# Multiplexage_Matrices.net
KiCad netlist of a schematic drawn in Altium Designer
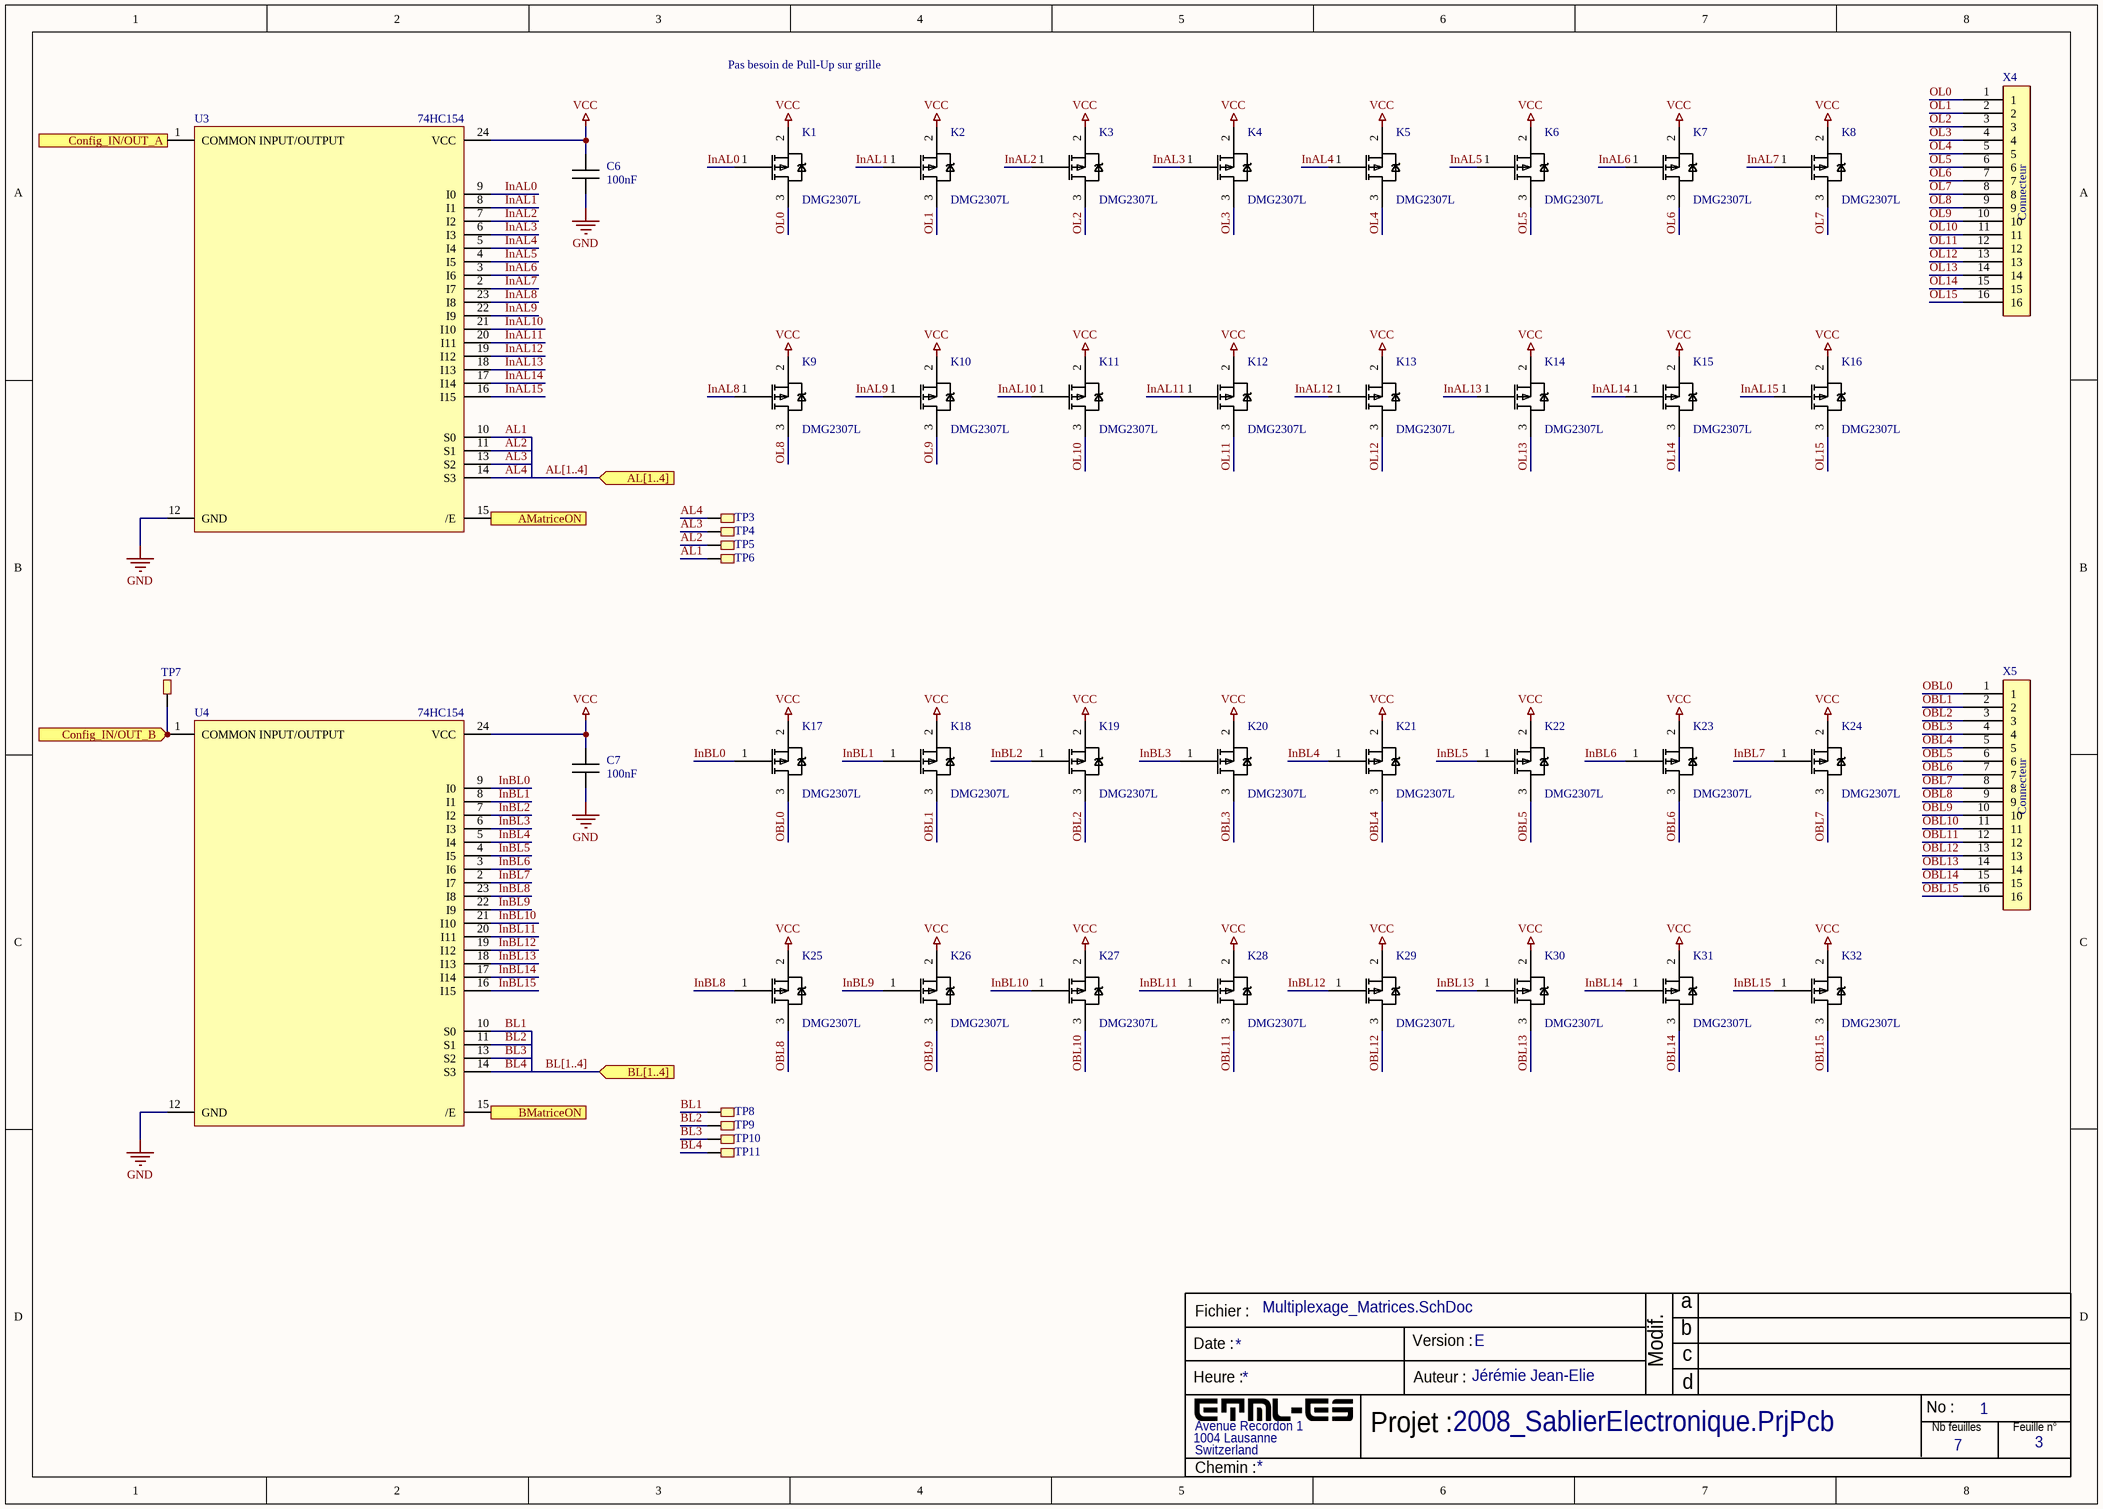
[diagram p0: Multiplexage_Matrices.SchDoc]

(export (version "E")
  (design (tool "Eeschema 10.0.6"))
  (components
    (comp (ref "C6")
      (value "100nF")
      (footprint "CAPC1608X08M")
      (description "CAPC 100nF X7R 50V 10% 1608 (0603 INCH)")
      (fields (field (name "VOLTAGE") "50V") (field (name "MANUFACTURER") "TDK"))
      (libsource (lib "ETML-ES") (part "CAP"))
    )
    (comp (ref "C7")
      (value "100nF")
      (footprint "CAPC1608X08M")
      (description "CAPC 100nF X7R 50V 10% 1608 (0603 INCH)")
      (fields (field (name "VOLTAGE") "50V") (field (name "MANUFACTURER") "TDK"))
      (libsource (lib "ETML-ES") (part "CAP"))
    )
    (comp (ref "K1")
      (value "DMG2307L")
      (footprint "SOT90P240X110-3M")
      (description "TRAN DMG2307L P-Channel Enhancement MOSFET 30V 2.5A")
      (fields (field (name "POWER") "760mW") (field (name "MANUFACTURER") "Diodes Incorporated"))
      (libsource (lib "ETML-ES") (part "TRAN-MOS-E-P-GSD"))
    )
    (comp (ref "K2")
      (value "DMG2307L")
      (footprint "SOT90P240X110-3M")
      (description "TRAN DMG2307L P-Channel Enhancement MOSFET 30V 2.5A")
      (fields (field (name "POWER") "760mW") (field (name "MANUFACTURER") "Diodes Incorporated"))
      (libsource (lib "ETML-ES") (part "TRAN-MOS-E-P-GSD"))
    )
    (comp (ref "K3")
      (value "DMG2307L")
      (footprint "SOT90P240X110-3M")
      (description "TRAN DMG2307L P-Channel Enhancement MOSFET 30V 2.5A")
      (fields (field (name "POWER") "760mW") (field (name "MANUFACTURER") "Diodes Incorporated"))
      (libsource (lib "ETML-ES") (part "TRAN-MOS-E-P-GSD"))
    )
    (comp (ref "K4")
      (value "DMG2307L")
      (footprint "SOT90P240X110-3M")
      (description "TRAN DMG2307L P-Channel Enhancement MOSFET 30V 2.5A")
      (fields (field (name "POWER") "760mW") (field (name "MANUFACTURER") "Diodes Incorporated"))
      (libsource (lib "ETML-ES") (part "TRAN-MOS-E-P-GSD"))
    )
    (comp (ref "K5")
      (value "DMG2307L")
      (footprint "SOT90P240X110-3M")
      (description "TRAN DMG2307L P-Channel Enhancement MOSFET 30V 2.5A")
      (fields (field (name "POWER") "760mW") (field (name "MANUFACTURER") "Diodes Incorporated"))
      (libsource (lib "ETML-ES") (part "TRAN-MOS-E-P-GSD"))
    )
    (comp (ref "K6")
      (value "DMG2307L")
      (footprint "SOT90P240X110-3M")
      (description "TRAN DMG2307L P-Channel Enhancement MOSFET 30V 2.5A")
      (fields (field (name "POWER") "760mW") (field (name "MANUFACTURER") "Diodes Incorporated"))
      (libsource (lib "ETML-ES") (part "TRAN-MOS-E-P-GSD"))
    )
    (comp (ref "K7")
      (value "DMG2307L")
      (footprint "SOT90P240X110-3M")
      (description "TRAN DMG2307L P-Channel Enhancement MOSFET 30V 2.5A")
      (fields (field (name "POWER") "760mW") (field (name "MANUFACTURER") "Diodes Incorporated"))
      (libsource (lib "ETML-ES") (part "TRAN-MOS-E-P-GSD"))
    )
    (comp (ref "K8")
      (value "DMG2307L")
      (footprint "SOT90P240X110-3M")
      (description "TRAN DMG2307L P-Channel Enhancement MOSFET 30V 2.5A")
      (fields (field (name "POWER") "760mW") (field (name "MANUFACTURER") "Diodes Incorporated"))
      (libsource (lib "ETML-ES") (part "TRAN-MOS-E-P-GSD"))
    )
    (comp (ref "K9")
      (value "DMG2307L")
      (footprint "SOT90P240X110-3M")
      (description "TRAN DMG2307L P-Channel Enhancement MOSFET 30V 2.5A")
      (fields (field (name "POWER") "760mW") (field (name "MANUFACTURER") "Diodes Incorporated"))
      (libsource (lib "ETML-ES") (part "TRAN-MOS-E-P-GSD"))
    )
    (comp (ref "K10")
      (value "DMG2307L")
      (footprint "SOT90P240X110-3M")
      (description "TRAN DMG2307L P-Channel Enhancement MOSFET 30V 2.5A")
      (fields (field (name "POWER") "760mW") (field (name "MANUFACTURER") "Diodes Incorporated"))
      (libsource (lib "ETML-ES") (part "TRAN-MOS-E-P-GSD"))
    )
    (comp (ref "K11")
      (value "DMG2307L")
      (footprint "SOT90P240X110-3M")
      (description "TRAN DMG2307L P-Channel Enhancement MOSFET 30V 2.5A")
      (fields (field (name "POWER") "760mW") (field (name "MANUFACTURER") "Diodes Incorporated"))
      (libsource (lib "ETML-ES") (part "TRAN-MOS-E-P-GSD"))
    )
    (comp (ref "K12")
      (value "DMG2307L")
      (footprint "SOT90P240X110-3M")
      (description "TRAN DMG2307L P-Channel Enhancement MOSFET 30V 2.5A")
      (fields (field (name "POWER") "760mW") (field (name "MANUFACTURER") "Diodes Incorporated"))
      (libsource (lib "ETML-ES") (part "TRAN-MOS-E-P-GSD"))
    )
    (comp (ref "K13")
      (value "DMG2307L")
      (footprint "SOT90P240X110-3M")
      (description "TRAN DMG2307L P-Channel Enhancement MOSFET 30V 2.5A")
      (fields (field (name "POWER") "760mW") (field (name "MANUFACTURER") "Diodes Incorporated"))
      (libsource (lib "ETML-ES") (part "TRAN-MOS-E-P-GSD"))
    )
    (comp (ref "K14")
      (value "DMG2307L")
      (footprint "SOT90P240X110-3M")
      (description "TRAN DMG2307L P-Channel Enhancement MOSFET 30V 2.5A")
      (fields (field (name "POWER") "760mW") (field (name "MANUFACTURER") "Diodes Incorporated"))
      (libsource (lib "ETML-ES") (part "TRAN-MOS-E-P-GSD"))
    )
    (comp (ref "K15")
      (value "DMG2307L")
      (footprint "SOT90P240X110-3M")
      (description "TRAN DMG2307L P-Channel Enhancement MOSFET 30V 2.5A")
      (fields (field (name "POWER") "760mW") (field (name "MANUFACTURER") "Diodes Incorporated"))
      (libsource (lib "ETML-ES") (part "TRAN-MOS-E-P-GSD"))
    )
    (comp (ref "K16")
      (value "DMG2307L")
      (footprint "SOT90P240X110-3M")
      (description "TRAN DMG2307L P-Channel Enhancement MOSFET 30V 2.5A")
      (fields (field (name "POWER") "760mW") (field (name "MANUFACTURER") "Diodes Incorporated"))
      (libsource (lib "ETML-ES") (part "TRAN-MOS-E-P-GSD"))
    )
    (comp (ref "K17")
      (value "DMG2307L")
      (footprint "SOT90P240X110-3M")
      (description "TRAN DMG2307L P-Channel Enhancement MOSFET 30V 2.5A")
      (fields (field (name "POWER") "760mW") (field (name "MANUFACTURER") "Diodes Incorporated"))
      (libsource (lib "ETML-ES") (part "TRAN-MOS-E-P-GSD"))
    )
    (comp (ref "K18")
      (value "DMG2307L")
      (footprint "SOT90P240X110-3M")
      (description "TRAN DMG2307L P-Channel Enhancement MOSFET 30V 2.5A")
      (fields (field (name "POWER") "760mW") (field (name "MANUFACTURER") "Diodes Incorporated"))
      (libsource (lib "ETML-ES") (part "TRAN-MOS-E-P-GSD"))
    )
    (comp (ref "K19")
      (value "DMG2307L")
      (footprint "SOT90P240X110-3M")
      (description "TRAN DMG2307L P-Channel Enhancement MOSFET 30V 2.5A")
      (fields (field (name "POWER") "760mW") (field (name "MANUFACTURER") "Diodes Incorporated"))
      (libsource (lib "ETML-ES") (part "TRAN-MOS-E-P-GSD"))
    )
    (comp (ref "K20")
      (value "DMG2307L")
      (footprint "SOT90P240X110-3M")
      (description "TRAN DMG2307L P-Channel Enhancement MOSFET 30V 2.5A")
      (fields (field (name "POWER") "760mW") (field (name "MANUFACTURER") "Diodes Incorporated"))
      (libsource (lib "ETML-ES") (part "TRAN-MOS-E-P-GSD"))
    )
    (comp (ref "K21")
      (value "DMG2307L")
      (footprint "SOT90P240X110-3M")
      (description "TRAN DMG2307L P-Channel Enhancement MOSFET 30V 2.5A")
      (fields (field (name "POWER") "760mW") (field (name "MANUFACTURER") "Diodes Incorporated"))
      (libsource (lib "ETML-ES") (part "TRAN-MOS-E-P-GSD"))
    )
    (comp (ref "K22")
      (value "DMG2307L")
      (footprint "SOT90P240X110-3M")
      (description "TRAN DMG2307L P-Channel Enhancement MOSFET 30V 2.5A")
      (fields (field (name "POWER") "760mW") (field (name "MANUFACTURER") "Diodes Incorporated"))
      (libsource (lib "ETML-ES") (part "TRAN-MOS-E-P-GSD"))
    )
    (comp (ref "K23")
      (value "DMG2307L")
      (footprint "SOT90P240X110-3M")
      (description "TRAN DMG2307L P-Channel Enhancement MOSFET 30V 2.5A")
      (fields (field (name "POWER") "760mW") (field (name "MANUFACTURER") "Diodes Incorporated"))
      (libsource (lib "ETML-ES") (part "TRAN-MOS-E-P-GSD"))
    )
    (comp (ref "K24")
      (value "DMG2307L")
      (footprint "SOT90P240X110-3M")
      (description "TRAN DMG2307L P-Channel Enhancement MOSFET 30V 2.5A")
      (fields (field (name "POWER") "760mW") (field (name "MANUFACTURER") "Diodes Incorporated"))
      (libsource (lib "ETML-ES") (part "TRAN-MOS-E-P-GSD"))
    )
    (comp (ref "K25")
      (value "DMG2307L")
      (footprint "SOT90P240X110-3M")
      (description "TRAN DMG2307L P-Channel Enhancement MOSFET 30V 2.5A")
      (fields (field (name "POWER") "760mW") (field (name "MANUFACTURER") "Diodes Incorporated"))
      (libsource (lib "ETML-ES") (part "TRAN-MOS-E-P-GSD"))
    )
    (comp (ref "K26")
      (value "DMG2307L")
      (footprint "SOT90P240X110-3M")
      (description "TRAN DMG2307L P-Channel Enhancement MOSFET 30V 2.5A")
      (fields (field (name "POWER") "760mW") (field (name "MANUFACTURER") "Diodes Incorporated"))
      (libsource (lib "ETML-ES") (part "TRAN-MOS-E-P-GSD"))
    )
    (comp (ref "K27")
      (value "DMG2307L")
      (footprint "SOT90P240X110-3M")
      (description "TRAN DMG2307L P-Channel Enhancement MOSFET 30V 2.5A")
      (fields (field (name "POWER") "760mW") (field (name "MANUFACTURER") "Diodes Incorporated"))
      (libsource (lib "ETML-ES") (part "TRAN-MOS-E-P-GSD"))
    )
    (comp (ref "K28")
      (value "DMG2307L")
      (footprint "SOT90P240X110-3M")
      (description "TRAN DMG2307L P-Channel Enhancement MOSFET 30V 2.5A")
      (fields (field (name "POWER") "760mW") (field (name "MANUFACTURER") "Diodes Incorporated"))
      (libsource (lib "ETML-ES") (part "TRAN-MOS-E-P-GSD"))
    )
    (comp (ref "K29")
      (value "DMG2307L")
      (footprint "SOT90P240X110-3M")
      (description "TRAN DMG2307L P-Channel Enhancement MOSFET 30V 2.5A")
      (fields (field (name "POWER") "760mW") (field (name "MANUFACTURER") "Diodes Incorporated"))
      (libsource (lib "ETML-ES") (part "TRAN-MOS-E-P-GSD"))
    )
    (comp (ref "K30")
      (value "DMG2307L")
      (footprint "SOT90P240X110-3M")
      (description "TRAN DMG2307L P-Channel Enhancement MOSFET 30V 2.5A")
      (fields (field (name "POWER") "760mW") (field (name "MANUFACTURER") "Diodes Incorporated"))
      (libsource (lib "ETML-ES") (part "TRAN-MOS-E-P-GSD"))
    )
    (comp (ref "K31")
      (value "DMG2307L")
      (footprint "SOT90P240X110-3M")
      (description "TRAN DMG2307L P-Channel Enhancement MOSFET 30V 2.5A")
      (fields (field (name "POWER") "760mW") (field (name "MANUFACTURER") "Diodes Incorporated"))
      (libsource (lib "ETML-ES") (part "TRAN-MOS-E-P-GSD"))
    )
    (comp (ref "K32")
      (value "DMG2307L")
      (footprint "SOT90P240X110-3M")
      (description "TRAN DMG2307L P-Channel Enhancement MOSFET 30V 2.5A")
      (fields (field (name "POWER") "760mW") (field (name "MANUFACTURER") "Diodes Incorporated"))
      (libsource (lib "ETML-ES") (part "TRAN-MOS-E-P-GSD"))
    )
    (comp (ref "TP3")
      (value "TestPoint")
      (footprint "KEYSTONE_5019")
      (libsource (lib "Schlib1") (part "TestPoint"))
    )
    (comp (ref "TP4")
      (value "TestPoint")
      (footprint "KEYSTONE_5019")
      (libsource (lib "Schlib1") (part "TestPoint"))
    )
    (comp (ref "TP5")
      (value "TestPoint")
      (footprint "KEYSTONE_5019")
      (libsource (lib "Schlib1") (part "TestPoint"))
    )
    (comp (ref "TP6")
      (value "TestPoint")
      (footprint "KEYSTONE_5019")
      (libsource (lib "Schlib1") (part "TestPoint"))
    )
    (comp (ref "TP7") (value "5019") (footprint "KEYSTONE_5019") (libsource (lib "") (part "TestPoint_1")))
    (comp (ref "TP8")
      (value "TestPoint")
      (footprint "KEYSTONE_5019")
      (libsource (lib "Schlib1") (part "TestPoint"))
    )
    (comp (ref "TP9")
      (value "TestPoint")
      (footprint "KEYSTONE_5019")
      (libsource (lib "Schlib1") (part "TestPoint"))
    )
    (comp (ref "TP10")
      (value "TestPoint")
      (footprint "KEYSTONE_5019")
      (libsource (lib "Schlib1") (part "TestPoint"))
    )
    (comp (ref "TP11")
      (value "TestPoint")
      (footprint "KEYSTONE_5019")
      (libsource (lib "Schlib1") (part "TestPoint"))
    )
    (comp (ref "U3")
      (value "74HC154")
      (footprint "SOP127P1030X265-24N")
      (libsource (lib "Schlib1") (part "74HC154"))
    )
    (comp (ref "U4")
      (value "74HC154")
      (footprint "SOP127P1030X265-24N")
      (libsource (lib "Schlib1") (part "74HC154"))
    )
    (comp (ref "X4")
      (value "~")
      (footprint "MOLEX_2x8")
      (libsource (lib "2008_SablierElectronique_SCHLIB") (part "Mâle DIN 8 x 8"))
    )
    (comp (ref "X5")
      (value "~")
      (footprint "MOLEX_2x8")
      (libsource (lib "2008_SablierElectronique_SCHLIB") (part "Mâle DIN 8 x 8"))
    )
  )
  (nets
    (net (code "1") (name "/AL1") (class "Default")
      (node (ref "TP6") (pin "1") (pinfunction "1_1") (pintype "passive"))
      (node (ref "U3") (pin "10") (pinfunction "S0_10") (pintype "passive"))
    )
    (net (code "2") (name "/AL2") (class "Default")
      (node (ref "TP5") (pin "1") (pinfunction "1_1") (pintype "passive"))
      (node (ref "U3") (pin "11") (pinfunction "S1_11") (pintype "passive"))
    )
    (net (code "3") (name "/AL3") (class "Default")
      (node (ref "TP4") (pin "1") (pinfunction "1_1") (pintype "passive"))
      (node (ref "U3") (pin "13") (pinfunction "S2_13") (pintype "passive"))
    )
    (net (code "4") (name "/AL4") (class "Default")
      (node (ref "TP3") (pin "1") (pinfunction "1_1") (pintype "passive"))
      (node (ref "U3") (pin "14") (pinfunction "S3_14") (pintype "passive"))
    )
    (net (code "6") (name "/AMatriceON") (class "Default")
      (node (ref "U3") (pin "15") (pinfunction "/E_15") (pintype "passive"))
    )
    (net (code "7") (name "/BL1") (class "Default")
      (node (ref "TP8") (pin "1") (pinfunction "1_1") (pintype "passive"))
      (node (ref "U4") (pin "10") (pinfunction "S0_10") (pintype "passive"))
    )
    (net (code "8") (name "/BL2") (class "Default")
      (node (ref "TP9") (pin "1") (pinfunction "1_1") (pintype "passive"))
      (node (ref "U4") (pin "11") (pinfunction "S1_11") (pintype "passive"))
    )
    (net (code "9") (name "/BL3") (class "Default")
      (node (ref "TP10") (pin "1") (pinfunction "1_1") (pintype "passive"))
      (node (ref "U4") (pin "13") (pinfunction "S2_13") (pintype "passive"))
    )
    (net (code "10") (name "/BL4") (class "Default")
      (node (ref "TP11") (pin "1") (pinfunction "1_1") (pintype "passive"))
      (node (ref "U4") (pin "14") (pinfunction "S3_14") (pintype "passive"))
    )
    (net (code "12") (name "/BMatriceON") (class "Default")
      (node (ref "U4") (pin "15") (pinfunction "/E_15") (pintype "passive"))
    )
    (net (code "13") (name "/Config_IN{slash}OUT_A") (class "Default")
      (node (ref "U3") (pin "1") (pinfunction "COMMON_INPUT/OUTPUT_1") (pintype "passive"))
    )
    (net (code "14") (name "/Config_IN{slash}OUT_B") (class "Default")
      (node (ref "TP7") (pin "1") (pinfunction "1_1") (pintype "passive"))
      (node (ref "U4") (pin "1") (pinfunction "COMMON_INPUT/OUTPUT_1") (pintype "passive"))
    )
    (net (code "15") (name "/InAL0") (class "Default")
      (node (ref "K1") (pin "1") (pinfunction "G_1") (pintype "passive"))
      (node (ref "U3") (pin "9") (pinfunction "I0_9") (pintype "passive"))
    )
    (net (code "16") (name "/InAL1") (class "Default")
      (node (ref "K2") (pin "1") (pinfunction "G_1") (pintype "passive"))
      (node (ref "U3") (pin "8") (pinfunction "I1_8") (pintype "passive"))
    )
    (net (code "17") (name "/InAL2") (class "Default")
      (node (ref "K3") (pin "1") (pinfunction "G_1") (pintype "passive"))
      (node (ref "U3") (pin "7") (pinfunction "I2_7") (pintype "passive"))
    )
    (net (code "18") (name "/InAL3") (class "Default")
      (node (ref "K4") (pin "1") (pinfunction "G_1") (pintype "passive"))
      (node (ref "U3") (pin "6") (pinfunction "I3_6") (pintype "passive"))
    )
    (net (code "19") (name "/InAL4") (class "Default")
      (node (ref "K5") (pin "1") (pinfunction "G_1") (pintype "passive"))
      (node (ref "U3") (pin "5") (pinfunction "I4_5") (pintype "passive"))
    )
    (net (code "20") (name "/InAL5") (class "Default")
      (node (ref "K6") (pin "1") (pinfunction "G_1") (pintype "passive"))
      (node (ref "U3") (pin "4") (pinfunction "I5_4") (pintype "passive"))
    )
    (net (code "21") (name "/InAL6") (class "Default")
      (node (ref "K7") (pin "1") (pinfunction "G_1") (pintype "passive"))
      (node (ref "U3") (pin "3") (pinfunction "I6_3") (pintype "passive"))
    )
    (net (code "22") (name "/InAL7") (class "Default")
      (node (ref "K8") (pin "1") (pinfunction "G_1") (pintype "passive"))
      (node (ref "U3") (pin "2") (pinfunction "I7_2") (pintype "passive"))
    )
    (net (code "23") (name "/InAL8") (class "Default")
      (node (ref "K9") (pin "1") (pinfunction "G_1") (pintype "passive"))
      (node (ref "U3") (pin "23") (pinfunction "I8_23") (pintype "passive"))
    )
    (net (code "24") (name "/InAL9") (class "Default")
      (node (ref "K10") (pin "1") (pinfunction "G_1") (pintype "passive"))
      (node (ref "U3") (pin "22") (pinfunction "I9_22") (pintype "passive"))
    )
    (net (code "25") (name "/InAL10") (class "Default")
      (node (ref "K11") (pin "1") (pinfunction "G_1") (pintype "passive"))
      (node (ref "U3") (pin "21") (pinfunction "I10_21") (pintype "passive"))
    )
    (net (code "26") (name "/InAL11") (class "Default")
      (node (ref "K12") (pin "1") (pinfunction "G_1") (pintype "passive"))
      (node (ref "U3") (pin "20") (pinfunction "I11_20") (pintype "passive"))
    )
    (net (code "27") (name "/InAL12") (class "Default")
      (node (ref "K13") (pin "1") (pinfunction "G_1") (pintype "passive"))
      (node (ref "U3") (pin "19") (pinfunction "I12_19") (pintype "passive"))
    )
    (net (code "28") (name "/InAL13") (class "Default")
      (node (ref "K14") (pin "1") (pinfunction "G_1") (pintype "passive"))
      (node (ref "U3") (pin "18") (pinfunction "I13_18") (pintype "passive"))
    )
    (net (code "29") (name "/InAL14") (class "Default")
      (node (ref "K15") (pin "1") (pinfunction "G_1") (pintype "passive"))
      (node (ref "U3") (pin "17") (pinfunction "I14_17") (pintype "passive"))
    )
    (net (code "30") (name "/InAL15") (class "Default")
      (node (ref "K16") (pin "1") (pinfunction "G_1") (pintype "passive"))
      (node (ref "U3") (pin "16") (pinfunction "I15_16") (pintype "passive"))
    )
    (net (code "31") (name "/InBL0") (class "Default")
      (node (ref "K17") (pin "1") (pinfunction "G_1") (pintype "passive"))
      (node (ref "U4") (pin "9") (pinfunction "I0_9") (pintype "passive"))
    )
    (net (code "32") (name "/InBL1") (class "Default")
      (node (ref "K18") (pin "1") (pinfunction "G_1") (pintype "passive"))
      (node (ref "U4") (pin "8") (pinfunction "I1_8") (pintype "passive"))
    )
    (net (code "33") (name "/InBL2") (class "Default")
      (node (ref "K19") (pin "1") (pinfunction "G_1") (pintype "passive"))
      (node (ref "U4") (pin "7") (pinfunction "I2_7") (pintype "passive"))
    )
    (net (code "34") (name "/InBL3") (class "Default")
      (node (ref "K20") (pin "1") (pinfunction "G_1") (pintype "passive"))
      (node (ref "U4") (pin "6") (pinfunction "I3_6") (pintype "passive"))
    )
    (net (code "35") (name "/InBL4") (class "Default")
      (node (ref "K21") (pin "1") (pinfunction "G_1") (pintype "passive"))
      (node (ref "U4") (pin "5") (pinfunction "I4_5") (pintype "passive"))
    )
    (net (code "36") (name "/InBL5") (class "Default")
      (node (ref "K22") (pin "1") (pinfunction "G_1") (pintype "passive"))
      (node (ref "U4") (pin "4") (pinfunction "I5_4") (pintype "passive"))
    )
    (net (code "37") (name "/InBL6") (class "Default")
      (node (ref "K23") (pin "1") (pinfunction "G_1") (pintype "passive"))
      (node (ref "U4") (pin "3") (pinfunction "I6_3") (pintype "passive"))
    )
    (net (code "38") (name "/InBL7") (class "Default")
      (node (ref "K24") (pin "1") (pinfunction "G_1") (pintype "passive"))
      (node (ref "U4") (pin "2") (pinfunction "I7_2") (pintype "passive"))
    )
    (net (code "39") (name "/InBL8") (class "Default")
      (node (ref "K25") (pin "1") (pinfunction "G_1") (pintype "passive"))
      (node (ref "U4") (pin "23") (pinfunction "I8_23") (pintype "passive"))
    )
    (net (code "40") (name "/InBL9") (class "Default")
      (node (ref "K26") (pin "1") (pinfunction "G_1") (pintype "passive"))
      (node (ref "U4") (pin "22") (pinfunction "I9_22") (pintype "passive"))
    )
    (net (code "41") (name "/InBL10") (class "Default")
      (node (ref "K27") (pin "1") (pinfunction "G_1") (pintype "passive"))
      (node (ref "U4") (pin "21") (pinfunction "I10_21") (pintype "passive"))
    )
    (net (code "42") (name "/InBL11") (class "Default")
      (node (ref "K28") (pin "1") (pinfunction "G_1") (pintype "passive"))
      (node (ref "U4") (pin "20") (pinfunction "I11_20") (pintype "passive"))
    )
    (net (code "43") (name "/InBL12") (class "Default")
      (node (ref "K29") (pin "1") (pinfunction "G_1") (pintype "passive"))
      (node (ref "U4") (pin "19") (pinfunction "I12_19") (pintype "passive"))
    )
    (net (code "44") (name "/InBL13") (class "Default")
      (node (ref "K30") (pin "1") (pinfunction "G_1") (pintype "passive"))
      (node (ref "U4") (pin "18") (pinfunction "I13_18") (pintype "passive"))
    )
    (net (code "45") (name "/InBL14") (class "Default")
      (node (ref "K31") (pin "1") (pinfunction "G_1") (pintype "passive"))
      (node (ref "U4") (pin "17") (pinfunction "I14_17") (pintype "passive"))
    )
    (net (code "46") (name "/InBL15") (class "Default")
      (node (ref "K32") (pin "1") (pinfunction "G_1") (pintype "passive"))
      (node (ref "U4") (pin "16") (pinfunction "I15_16") (pintype "passive"))
    )
    (net (code "47") (name "/OBL0") (class "Default")
      (node (ref "K17") (pin "3") (pinfunction "D_3") (pintype "passive"))
      (node (ref "X5") (pin "1") (pinfunction "1_1") (pintype "passive"))
    )
    (net (code "48") (name "/OBL1") (class "Default")
      (node (ref "K18") (pin "3") (pinfunction "D_3") (pintype "passive"))
      (node (ref "X5") (pin "2") (pinfunction "2_2") (pintype "passive"))
    )
    (net (code "49") (name "/OBL2") (class "Default")
      (node (ref "K19") (pin "3") (pinfunction "D_3") (pintype "passive"))
      (node (ref "X5") (pin "3") (pinfunction "3_3") (pintype "passive"))
    )
    (net (code "50") (name "/OBL3") (class "Default")
      (node (ref "K20") (pin "3") (pinfunction "D_3") (pintype "passive"))
      (node (ref "X5") (pin "4") (pinfunction "4_4") (pintype "passive"))
    )
    (net (code "51") (name "/OBL4") (class "Default")
      (node (ref "K21") (pin "3") (pinfunction "D_3") (pintype "passive"))
      (node (ref "X5") (pin "5") (pinfunction "5_5") (pintype "passive"))
    )
    (net (code "52") (name "/OBL5") (class "Default")
      (node (ref "K22") (pin "3") (pinfunction "D_3") (pintype "passive"))
      (node (ref "X5") (pin "6") (pinfunction "6_6") (pintype "passive"))
    )
    (net (code "53") (name "/OBL6") (class "Default")
      (node (ref "K23") (pin "3") (pinfunction "D_3") (pintype "passive"))
      (node (ref "X5") (pin "7") (pinfunction "7_7") (pintype "passive"))
    )
    (net (code "54") (name "/OBL7") (class "Default")
      (node (ref "K24") (pin "3") (pinfunction "D_3") (pintype "passive"))
      (node (ref "X5") (pin "8") (pinfunction "8_8") (pintype "passive"))
    )
    (net (code "55") (name "/OBL8") (class "Default")
      (node (ref "K25") (pin "3") (pinfunction "D_3") (pintype "passive"))
      (node (ref "X5") (pin "9") (pinfunction "9_9") (pintype "passive"))
    )
    (net (code "56") (name "/OBL9") (class "Default")
      (node (ref "K26") (pin "3") (pinfunction "D_3") (pintype "passive"))
      (node (ref "X5") (pin "10") (pinfunction "10_10") (pintype "passive"))
    )
    (net (code "57") (name "/OBL10") (class "Default")
      (node (ref "K27") (pin "3") (pinfunction "D_3") (pintype "passive"))
      (node (ref "X5") (pin "11") (pinfunction "11_11") (pintype "passive"))
    )
    (net (code "58") (name "/OBL11") (class "Default")
      (node (ref "K28") (pin "3") (pinfunction "D_3") (pintype "passive"))
      (node (ref "X5") (pin "12") (pinfunction "12_12") (pintype "passive"))
    )
    (net (code "59") (name "/OBL12") (class "Default")
      (node (ref "K29") (pin "3") (pinfunction "D_3") (pintype "passive"))
      (node (ref "X5") (pin "13") (pinfunction "13_13") (pintype "passive"))
    )
    (net (code "60") (name "/OBL13") (class "Default")
      (node (ref "K30") (pin "3") (pinfunction "D_3") (pintype "passive"))
      (node (ref "X5") (pin "14") (pinfunction "14_14") (pintype "passive"))
    )
    (net (code "61") (name "/OBL14") (class "Default")
      (node (ref "K31") (pin "3") (pinfunction "D_3") (pintype "passive"))
      (node (ref "X5") (pin "15") (pinfunction "15_15") (pintype "passive"))
    )
    (net (code "62") (name "/OBL15") (class "Default")
      (node (ref "K32") (pin "3") (pinfunction "D_3") (pintype "passive"))
      (node (ref "X5") (pin "16") (pinfunction "16_16") (pintype "passive"))
    )
    (net (code "63") (name "/OL0") (class "Default")
      (node (ref "K1") (pin "3") (pinfunction "D_3") (pintype "passive"))
      (node (ref "X4") (pin "1") (pinfunction "1_1") (pintype "passive"))
    )
    (net (code "64") (name "/OL1") (class "Default")
      (node (ref "K2") (pin "3") (pinfunction "D_3") (pintype "passive"))
      (node (ref "X4") (pin "2") (pinfunction "2_2") (pintype "passive"))
    )
    (net (code "65") (name "/OL2") (class "Default")
      (node (ref "K3") (pin "3") (pinfunction "D_3") (pintype "passive"))
      (node (ref "X4") (pin "3") (pinfunction "3_3") (pintype "passive"))
    )
    (net (code "66") (name "/OL3") (class "Default")
      (node (ref "K4") (pin "3") (pinfunction "D_3") (pintype "passive"))
      (node (ref "X4") (pin "4") (pinfunction "4_4") (pintype "passive"))
    )
    (net (code "67") (name "/OL4") (class "Default")
      (node (ref "K5") (pin "3") (pinfunction "D_3") (pintype "passive"))
      (node (ref "X4") (pin "5") (pinfunction "5_5") (pintype "passive"))
    )
    (net (code "68") (name "/OL5") (class "Default")
      (node (ref "K6") (pin "3") (pinfunction "D_3") (pintype "passive"))
      (node (ref "X4") (pin "6") (pinfunction "6_6") (pintype "passive"))
    )
    (net (code "69") (name "/OL6") (class "Default")
      (node (ref "K7") (pin "3") (pinfunction "D_3") (pintype "passive"))
      (node (ref "X4") (pin "7") (pinfunction "7_7") (pintype "passive"))
    )
    (net (code "70") (name "/OL7") (class "Default")
      (node (ref "K8") (pin "3") (pinfunction "D_3") (pintype "passive"))
      (node (ref "X4") (pin "8") (pinfunction "8_8") (pintype "passive"))
    )
    (net (code "71") (name "/OL8") (class "Default")
      (node (ref "K9") (pin "3") (pinfunction "D_3") (pintype "passive"))
      (node (ref "X4") (pin "9") (pinfunction "9_9") (pintype "passive"))
    )
    (net (code "72") (name "/OL9") (class "Default")
      (node (ref "K10") (pin "3") (pinfunction "D_3") (pintype "passive"))
      (node (ref "X4") (pin "10") (pinfunction "10_10") (pintype "passive"))
    )
    (net (code "73") (name "/OL10") (class "Default")
      (node (ref "K11") (pin "3") (pinfunction "D_3") (pintype "passive"))
      (node (ref "X4") (pin "11") (pinfunction "11_11") (pintype "passive"))
    )
    (net (code "74") (name "/OL11") (class "Default")
      (node (ref "K12") (pin "3") (pinfunction "D_3") (pintype "passive"))
      (node (ref "X4") (pin "12") (pinfunction "12_12") (pintype "passive"))
    )
    (net (code "75") (name "/OL12") (class "Default")
      (node (ref "K13") (pin "3") (pinfunction "D_3") (pintype "passive"))
      (node (ref "X4") (pin "13") (pinfunction "13_13") (pintype "passive"))
    )
    (net (code "76") (name "/OL13") (class "Default")
      (node (ref "K14") (pin "3") (pinfunction "D_3") (pintype "passive"))
      (node (ref "X4") (pin "14") (pinfunction "14_14") (pintype "passive"))
    )
    (net (code "77") (name "/OL14") (class "Default")
      (node (ref "K15") (pin "3") (pinfunction "D_3") (pintype "passive"))
      (node (ref "X4") (pin "15") (pinfunction "15_15") (pintype "passive"))
    )
    (net (code "78") (name "/OL15") (class "Default")
      (node (ref "K16") (pin "3") (pinfunction "D_3") (pintype "passive"))
      (node (ref "X4") (pin "16") (pinfunction "16_16") (pintype "passive"))
    )
    (net (code "79") (name "GND") (class "Default")
      (node (ref "C6") (pin "1") (pinfunction "1_1") (pintype "passive"))
      (node (ref "C7") (pin "1") (pinfunction "1_1") (pintype "passive"))
      (node (ref "U3") (pin "12") (pinfunction "GND_12") (pintype "passive"))
      (node (ref "U4") (pin "12") (pinfunction "GND_12") (pintype "passive"))
    )
    (net (code "80") (name "VCC") (class "Default")
      (node (ref "C6") (pin "2") (pinfunction "2_2") (pintype "passive"))
      (node (ref "C7") (pin "2") (pinfunction "2_2") (pintype "passive"))
      (node (ref "K1") (pin "2") (pinfunction "S_2") (pintype "passive"))
      (node (ref "K10") (pin "2") (pinfunction "S_2") (pintype "passive"))
      (node (ref "K11") (pin "2") (pinfunction "S_2") (pintype "passive"))
      (node (ref "K12") (pin "2") (pinfunction "S_2") (pintype "passive"))
      (node (ref "K13") (pin "2") (pinfunction "S_2") (pintype "passive"))
      (node (ref "K14") (pin "2") (pinfunction "S_2") (pintype "passive"))
      (node (ref "K15") (pin "2") (pinfunction "S_2") (pintype "passive"))
      (node (ref "K16") (pin "2") (pinfunction "S_2") (pintype "passive"))
      (node (ref "K17") (pin "2") (pinfunction "S_2") (pintype "passive"))
      (node (ref "K18") (pin "2") (pinfunction "S_2") (pintype "passive"))
      (node (ref "K19") (pin "2") (pinfunction "S_2") (pintype "passive"))
      (node (ref "K2") (pin "2") (pinfunction "S_2") (pintype "passive"))
      (node (ref "K20") (pin "2") (pinfunction "S_2") (pintype "passive"))
      (node (ref "K21") (pin "2") (pinfunction "S_2") (pintype "passive"))
      (node (ref "K22") (pin "2") (pinfunction "S_2") (pintype "passive"))
      (node (ref "K23") (pin "2") (pinfunction "S_2") (pintype "passive"))
      (node (ref "K24") (pin "2") (pinfunction "S_2") (pintype "passive"))
      (node (ref "K25") (pin "2") (pinfunction "S_2") (pintype "passive"))
      (node (ref "K26") (pin "2") (pinfunction "S_2") (pintype "passive"))
      (node (ref "K27") (pin "2") (pinfunction "S_2") (pintype "passive"))
      (node (ref "K28") (pin "2") (pinfunction "S_2") (pintype "passive"))
      (node (ref "K29") (pin "2") (pinfunction "S_2") (pintype "passive"))
      (node (ref "K3") (pin "2") (pinfunction "S_2") (pintype "passive"))
      (node (ref "K30") (pin "2") (pinfunction "S_2") (pintype "passive"))
      (node (ref "K31") (pin "2") (pinfunction "S_2") (pintype "passive"))
      (node (ref "K32") (pin "2") (pinfunction "S_2") (pintype "passive"))
      (node (ref "K4") (pin "2") (pinfunction "S_2") (pintype "passive"))
      (node (ref "K5") (pin "2") (pinfunction "S_2") (pintype "passive"))
      (node (ref "K6") (pin "2") (pinfunction "S_2") (pintype "passive"))
      (node (ref "K7") (pin "2") (pinfunction "S_2") (pintype "passive"))
      (node (ref "K8") (pin "2") (pinfunction "S_2") (pintype "passive"))
      (node (ref "K9") (pin "2") (pinfunction "S_2") (pintype "passive"))
      (node (ref "U3") (pin "24") (pinfunction "VCC_24") (pintype "passive"))
      (node (ref "U4") (pin "24") (pinfunction "VCC_24") (pintype "passive"))
    )
  )
)
